# 4x4keyboard.net
KiCad netlist of a schematic drawn in EAGLE
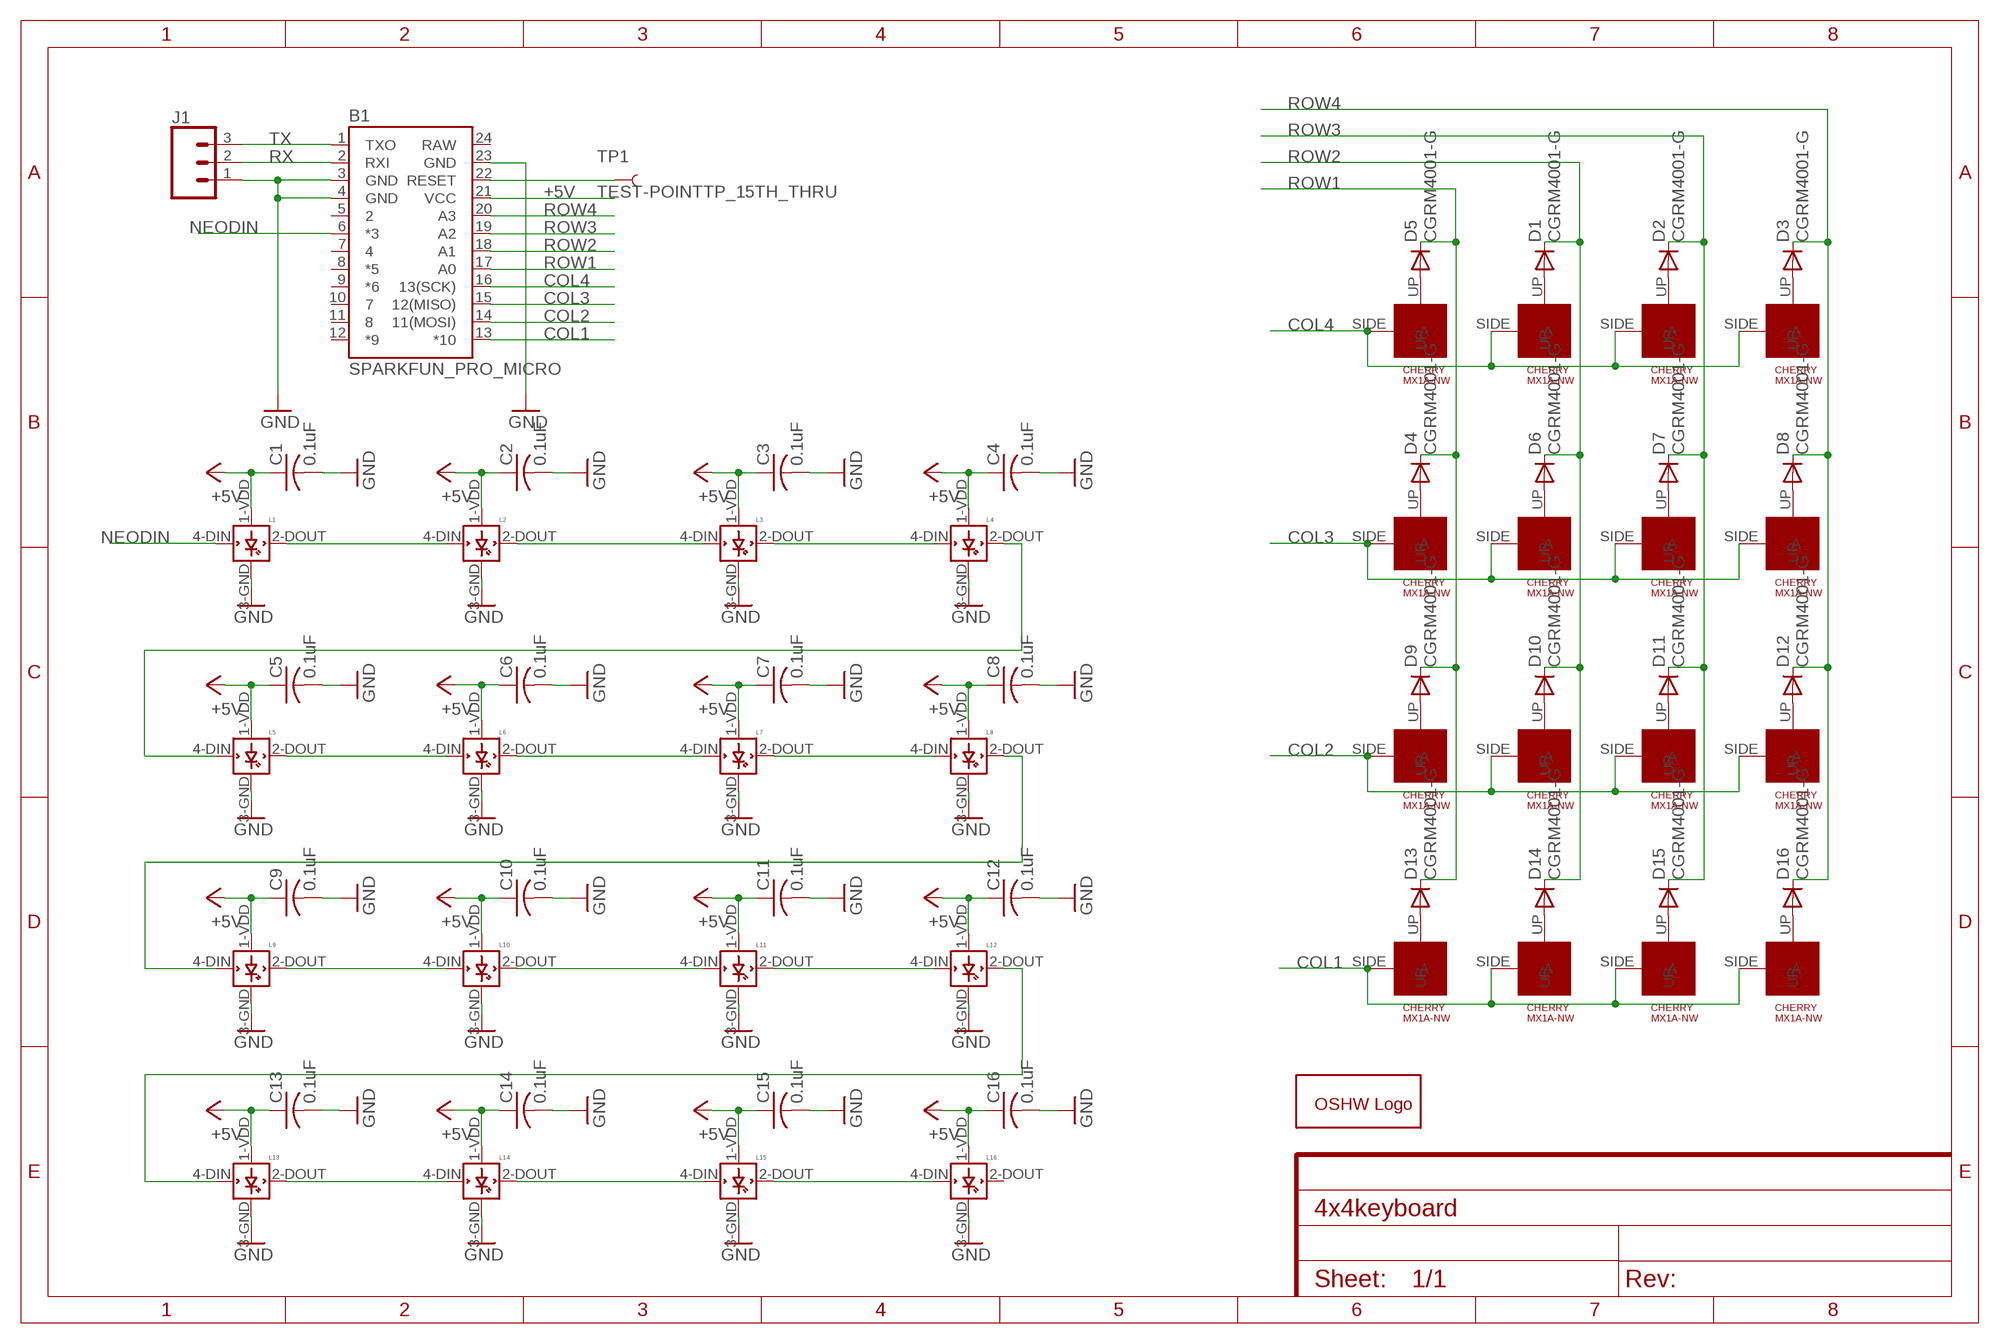
[diagram p0: schematic, sheet 1]

(export (version "E")
  (design (tool "Eeschema 10.0.6"))
  (components
    (comp (ref "B1")
      (value "SPARKFUN_PRO_MICRO")
      (footprint "eagle-import:SPARKFUN_PRO_MICRO")
      (libsource (lib "eagle-import") (part "SPARKFUN_PRO_MICRO"))
    )
    (comp (ref "C1")
      (value "0.1uF")
      (footprint "eagle-import:C0603")
      (libsource (lib "eagle-import") (part "C-USC0603"))
    )
    (comp (ref "C2")
      (value "0.1uF")
      (footprint "eagle-import:C0603")
      (libsource (lib "eagle-import") (part "C-USC0603"))
    )
    (comp (ref "C3")
      (value "0.1uF")
      (footprint "eagle-import:C0603")
      (libsource (lib "eagle-import") (part "C-USC0603"))
    )
    (comp (ref "C4")
      (value "0.1uF")
      (footprint "eagle-import:C0603")
      (libsource (lib "eagle-import") (part "C-USC0603"))
    )
    (comp (ref "C5")
      (value "0.1uF")
      (footprint "eagle-import:C0603")
      (libsource (lib "eagle-import") (part "C-USC0603"))
    )
    (comp (ref "C6")
      (value "0.1uF")
      (footprint "eagle-import:C0603")
      (libsource (lib "eagle-import") (part "C-USC0603"))
    )
    (comp (ref "C7")
      (value "0.1uF")
      (footprint "eagle-import:C0603")
      (libsource (lib "eagle-import") (part "C-USC0603"))
    )
    (comp (ref "C8")
      (value "0.1uF")
      (footprint "eagle-import:C0603")
      (libsource (lib "eagle-import") (part "C-USC0603"))
    )
    (comp (ref "C9")
      (value "0.1uF")
      (footprint "eagle-import:C0603")
      (libsource (lib "eagle-import") (part "C-USC0603"))
    )
    (comp (ref "C10")
      (value "0.1uF")
      (footprint "eagle-import:C0603")
      (libsource (lib "eagle-import") (part "C-USC0603"))
    )
    (comp (ref "C11")
      (value "0.1uF")
      (footprint "eagle-import:C0603")
      (libsource (lib "eagle-import") (part "C-USC0603"))
    )
    (comp (ref "C12")
      (value "0.1uF")
      (footprint "eagle-import:C0603")
      (libsource (lib "eagle-import") (part "C-USC0603"))
    )
    (comp (ref "C13")
      (value "0.1uF")
      (footprint "eagle-import:C0603")
      (libsource (lib "eagle-import") (part "C-USC0603"))
    )
    (comp (ref "C14")
      (value "0.1uF")
      (footprint "eagle-import:C0603")
      (libsource (lib "eagle-import") (part "C-USC0603"))
    )
    (comp (ref "C15")
      (value "0.1uF")
      (footprint "eagle-import:C0603")
      (libsource (lib "eagle-import") (part "C-USC0603"))
    )
    (comp (ref "C16")
      (value "0.1uF")
      (footprint "eagle-import:C0603")
      (libsource (lib "eagle-import") (part "C-USC0603"))
    )
    (comp (ref "D1")
      (value "CGRM4001-G")
      (footprint "eagle-import:SOD-123_MINI-SMA")
      (libsource (lib "eagle-import") (part "CGRM400-G1"))
    )
    (comp (ref "D2")
      (value "CGRM4001-G")
      (footprint "eagle-import:SOD-123_MINI-SMA")
      (libsource (lib "eagle-import") (part "CGRM400-G1"))
    )
    (comp (ref "D3")
      (value "CGRM4001-G")
      (footprint "eagle-import:SOD-123_MINI-SMA")
      (libsource (lib "eagle-import") (part "CGRM400-G1"))
    )
    (comp (ref "D4")
      (value "CGRM4001-G")
      (footprint "eagle-import:SOD-123_MINI-SMA")
      (libsource (lib "eagle-import") (part "CGRM400-G1"))
    )
    (comp (ref "D5")
      (value "CGRM4001-G")
      (footprint "eagle-import:SOD-123_MINI-SMA")
      (libsource (lib "eagle-import") (part "CGRM400-G1"))
    )
    (comp (ref "D6")
      (value "CGRM4001-G")
      (footprint "eagle-import:SOD-123_MINI-SMA")
      (libsource (lib "eagle-import") (part "CGRM400-G1"))
    )
    (comp (ref "D7")
      (value "CGRM4001-G")
      (footprint "eagle-import:SOD-123_MINI-SMA")
      (libsource (lib "eagle-import") (part "CGRM400-G1"))
    )
    (comp (ref "D8")
      (value "CGRM4001-G")
      (footprint "eagle-import:SOD-123_MINI-SMA")
      (libsource (lib "eagle-import") (part "CGRM400-G1"))
    )
    (comp (ref "D9")
      (value "CGRM4001-G")
      (footprint "eagle-import:SOD-123_MINI-SMA")
      (libsource (lib "eagle-import") (part "CGRM400-G1"))
    )
    (comp (ref "D10")
      (value "CGRM4001-G")
      (footprint "eagle-import:SOD-123_MINI-SMA")
      (libsource (lib "eagle-import") (part "CGRM400-G1"))
    )
    (comp (ref "D11")
      (value "CGRM4001-G")
      (footprint "eagle-import:SOD-123_MINI-SMA")
      (libsource (lib "eagle-import") (part "CGRM400-G1"))
    )
    (comp (ref "D12")
      (value "CGRM4001-G")
      (footprint "eagle-import:SOD-123_MINI-SMA")
      (libsource (lib "eagle-import") (part "CGRM400-G1"))
    )
    (comp (ref "D13")
      (value "CGRM4001-G")
      (footprint "eagle-import:SOD-123_MINI-SMA")
      (libsource (lib "eagle-import") (part "CGRM400-G1"))
    )
    (comp (ref "D14")
      (value "CGRM4001-G")
      (footprint "eagle-import:SOD-123_MINI-SMA")
      (libsource (lib "eagle-import") (part "CGRM400-G1"))
    )
    (comp (ref "D15")
      (value "CGRM4001-G")
      (footprint "eagle-import:SOD-123_MINI-SMA")
      (libsource (lib "eagle-import") (part "CGRM400-G1"))
    )
    (comp (ref "D16")
      (value "CGRM4001-G")
      (footprint "eagle-import:SOD-123_MINI-SMA")
      (libsource (lib "eagle-import") (part "CGRM400-G1"))
    )
    (comp (ref "GOLD_ORB_SM1")
      (value "OSHWLOGOLOGO5MM")
      (footprint "eagle-import:OSHW_5MM")
      (libsource (lib "eagle-import") (part "OSHWLOGOLOGO5MM"))
    )
    (comp (ref "J1")
      (value "CONN_03LOCK")
      (footprint "eagle-import:1X03_LOCK")
      (libsource (lib "eagle-import") (part "CONN_03LOCK"))
    )
    (comp (ref "L1")
      (value "WS2812B")
      (footprint "eagle-import:WS2812B")
      (libsource (lib "eagle-import") (part "WS2812B"))
    )
    (comp (ref "L2")
      (value "WS2812B")
      (footprint "eagle-import:WS2812B")
      (libsource (lib "eagle-import") (part "WS2812B"))
    )
    (comp (ref "L3")
      (value "WS2812B")
      (footprint "eagle-import:WS2812B")
      (libsource (lib "eagle-import") (part "WS2812B"))
    )
    (comp (ref "L4")
      (value "WS2812B")
      (footprint "eagle-import:WS2812B")
      (libsource (lib "eagle-import") (part "WS2812B"))
    )
    (comp (ref "L5")
      (value "WS2812B")
      (footprint "eagle-import:WS2812B")
      (libsource (lib "eagle-import") (part "WS2812B"))
    )
    (comp (ref "L6")
      (value "WS2812B")
      (footprint "eagle-import:WS2812B")
      (libsource (lib "eagle-import") (part "WS2812B"))
    )
    (comp (ref "L7")
      (value "WS2812B")
      (footprint "eagle-import:WS2812B")
      (libsource (lib "eagle-import") (part "WS2812B"))
    )
    (comp (ref "L8")
      (value "WS2812B")
      (footprint "eagle-import:WS2812B")
      (libsource (lib "eagle-import") (part "WS2812B"))
    )
    (comp (ref "L9")
      (value "WS2812B")
      (footprint "eagle-import:WS2812B")
      (libsource (lib "eagle-import") (part "WS2812B"))
    )
    (comp (ref "L10")
      (value "WS2812B")
      (footprint "eagle-import:WS2812B")
      (libsource (lib "eagle-import") (part "WS2812B"))
    )
    (comp (ref "L11")
      (value "WS2812B")
      (footprint "eagle-import:WS2812B")
      (libsource (lib "eagle-import") (part "WS2812B"))
    )
    (comp (ref "L12")
      (value "WS2812B")
      (footprint "eagle-import:WS2812B")
      (libsource (lib "eagle-import") (part "WS2812B"))
    )
    (comp (ref "L13")
      (value "WS2812B")
      (footprint "eagle-import:WS2812B")
      (libsource (lib "eagle-import") (part "WS2812B"))
    )
    (comp (ref "L14")
      (value "WS2812B")
      (footprint "eagle-import:WS2812B")
      (libsource (lib "eagle-import") (part "WS2812B"))
    )
    (comp (ref "L15")
      (value "WS2812B")
      (footprint "eagle-import:WS2812B")
      (libsource (lib "eagle-import") (part "WS2812B"))
    )
    (comp (ref "L16")
      (value "WS2812B")
      (footprint "eagle-import:WS2812B")
      (libsource (lib "eagle-import") (part "WS2812B"))
    )
    (comp (ref "TP1")
      (value "TEST-POINTTP_15TH_THRU")
      (footprint "eagle-import:TP_15TH")
      (libsource (lib "eagle-import") (part "TEST-POINTTP_15TH_THRU"))
    )
    (comp (ref "U$1")
      (value "CHERRY-MX1A-E1NW")
      (footprint "eagle-import:CHERRYMX-NN")
      (libsource (lib "eagle-import") (part "CHERRY-MX1A-E1NW"))
    )
    (comp (ref "U$2")
      (value "CHERRY-MX1A-E1NW")
      (footprint "eagle-import:CHERRYMX-NN")
      (libsource (lib "eagle-import") (part "CHERRY-MX1A-E1NW"))
    )
    (comp (ref "U$3")
      (value "CHERRY-MX1A-E1NW")
      (footprint "eagle-import:CHERRYMX-NN")
      (libsource (lib "eagle-import") (part "CHERRY-MX1A-E1NW"))
    )
    (comp (ref "U$4")
      (value "CHERRY-MX1A-E1NW")
      (footprint "eagle-import:CHERRYMX-NN")
      (libsource (lib "eagle-import") (part "CHERRY-MX1A-E1NW"))
    )
    (comp (ref "U$7")
      (value "CHERRY-MX1A-E1NW")
      (footprint "eagle-import:CHERRYMX-NN")
      (libsource (lib "eagle-import") (part "CHERRY-MX1A-E1NW"))
    )
    (comp (ref "U$8")
      (value "CHERRY-MX1A-E1NW")
      (footprint "eagle-import:CHERRYMX-NN")
      (libsource (lib "eagle-import") (part "CHERRY-MX1A-E1NW"))
    )
    (comp (ref "U$9")
      (value "CHERRY-MX1A-E1NW")
      (footprint "eagle-import:CHERRYMX-NN")
      (libsource (lib "eagle-import") (part "CHERRY-MX1A-E1NW"))
    )
    (comp (ref "U$10")
      (value "CHERRY-MX1A-E1NW")
      (footprint "eagle-import:CHERRYMX-NN")
      (libsource (lib "eagle-import") (part "CHERRY-MX1A-E1NW"))
    )
    (comp (ref "U$19")
      (value "CHERRY-MX1A-E1NW")
      (footprint "eagle-import:CHERRYMX-NN")
      (libsource (lib "eagle-import") (part "CHERRY-MX1A-E1NW"))
    )
    (comp (ref "U$20")
      (value "CHERRY-MX1A-E1NW")
      (footprint "eagle-import:CHERRYMX-NN")
      (libsource (lib "eagle-import") (part "CHERRY-MX1A-E1NW"))
    )
    (comp (ref "U$21")
      (value "CHERRY-MX1A-E1NW")
      (footprint "eagle-import:CHERRYMX-NN")
      (libsource (lib "eagle-import") (part "CHERRY-MX1A-E1NW"))
    )
    (comp (ref "U$22")
      (value "CHERRY-MX1A-E1NW")
      (footprint "eagle-import:CHERRYMX-NN")
      (libsource (lib "eagle-import") (part "CHERRY-MX1A-E1NW"))
    )
    (comp (ref "U$25")
      (value "CHERRY-MX1A-E1NW")
      (footprint "eagle-import:CHERRYMX-NN")
      (libsource (lib "eagle-import") (part "CHERRY-MX1A-E1NW"))
    )
    (comp (ref "U$26")
      (value "CHERRY-MX1A-E1NW")
      (footprint "eagle-import:CHERRYMX-NN")
      (libsource (lib "eagle-import") (part "CHERRY-MX1A-E1NW"))
    )
    (comp (ref "U$27")
      (value "CHERRY-MX1A-E1NW")
      (footprint "eagle-import:CHERRYMX-NN")
      (libsource (lib "eagle-import") (part "CHERRY-MX1A-E1NW"))
    )
    (comp (ref "U$28")
      (value "CHERRY-MX1A-E1NW")
      (footprint "eagle-import:CHERRYMX-NN")
      (libsource (lib "eagle-import") (part "CHERRY-MX1A-E1NW"))
    )
  )
  (nets
    (net (code "1") (name "+5V") (class "Default")
      (node (ref "B1") (pin "21") (pinfunction "VCC_21") (pintype "power_in"))
      (node (ref "C1") (pin "1") (pinfunction "1_1") (pintype "passive"))
      (node (ref "C10") (pin "1") (pinfunction "1_1") (pintype "passive"))
      (node (ref "C11") (pin "1") (pinfunction "1_1") (pintype "passive"))
      (node (ref "C12") (pin "1") (pinfunction "1_1") (pintype "passive"))
      (node (ref "C13") (pin "1") (pinfunction "1_1") (pintype "passive"))
      (node (ref "C14") (pin "1") (pinfunction "1_1") (pintype "passive"))
      (node (ref "C15") (pin "1") (pinfunction "1_1") (pintype "passive"))
      (node (ref "C16") (pin "1") (pinfunction "1_1") (pintype "passive"))
      (node (ref "C2") (pin "1") (pinfunction "1_1") (pintype "passive"))
      (node (ref "C3") (pin "1") (pinfunction "1_1") (pintype "passive"))
      (node (ref "C4") (pin "1") (pinfunction "1_1") (pintype "passive"))
      (node (ref "C5") (pin "1") (pinfunction "1_1") (pintype "passive"))
      (node (ref "C6") (pin "1") (pinfunction "1_1") (pintype "passive"))
      (node (ref "C7") (pin "1") (pinfunction "1_1") (pintype "passive"))
      (node (ref "C8") (pin "1") (pinfunction "1_1") (pintype "passive"))
      (node (ref "C9") (pin "1") (pinfunction "1_1") (pintype "passive"))
      (node (ref "L1") (pin "1-VDD") (pinfunction "VDD_1-VDD") (pintype "bidirectional"))
      (node (ref "L10") (pin "1-VDD") (pinfunction "VDD_1-VDD") (pintype "bidirectional"))
      (node (ref "L11") (pin "1-VDD") (pinfunction "VDD_1-VDD") (pintype "bidirectional"))
      (node (ref "L12") (pin "1-VDD") (pinfunction "VDD_1-VDD") (pintype "bidirectional"))
      (node (ref "L13") (pin "1-VDD") (pinfunction "VDD_1-VDD") (pintype "bidirectional"))
      (node (ref "L14") (pin "1-VDD") (pinfunction "VDD_1-VDD") (pintype "bidirectional"))
      (node (ref "L15") (pin "1-VDD") (pinfunction "VDD_1-VDD") (pintype "bidirectional"))
      (node (ref "L16") (pin "1-VDD") (pinfunction "VDD_1-VDD") (pintype "bidirectional"))
      (node (ref "L2") (pin "1-VDD") (pinfunction "VDD_1-VDD") (pintype "bidirectional"))
      (node (ref "L3") (pin "1-VDD") (pinfunction "VDD_1-VDD") (pintype "bidirectional"))
      (node (ref "L4") (pin "1-VDD") (pinfunction "VDD_1-VDD") (pintype "bidirectional"))
      (node (ref "L5") (pin "1-VDD") (pinfunction "VDD_1-VDD") (pintype "bidirectional"))
      (node (ref "L6") (pin "1-VDD") (pinfunction "VDD_1-VDD") (pintype "bidirectional"))
      (node (ref "L7") (pin "1-VDD") (pinfunction "VDD_1-VDD") (pintype "bidirectional"))
      (node (ref "L8") (pin "1-VDD") (pinfunction "VDD_1-VDD") (pintype "bidirectional"))
      (node (ref "L9") (pin "1-VDD") (pinfunction "VDD_1-VDD") (pintype "bidirectional"))
    )
    (net (code "2") (name "/COL1") (class "Default")
      (node (ref "B1") (pin "13") (pinfunction "*10_13") (pintype "bidirectional"))
      (node (ref "U$25") (pin "SIDE") (pinfunction "A_SIDE") (pintype "bidirectional"))
      (node (ref "U$26") (pin "SIDE") (pinfunction "A_SIDE") (pintype "bidirectional"))
      (node (ref "U$27") (pin "SIDE") (pinfunction "A_SIDE") (pintype "bidirectional"))
      (node (ref "U$28") (pin "SIDE") (pinfunction "A_SIDE") (pintype "bidirectional"))
    )
    (net (code "3") (name "/COL2") (class "Default")
      (node (ref "B1") (pin "14") (pinfunction "11(MOSI)_14") (pintype "bidirectional"))
      (node (ref "U$10") (pin "SIDE") (pinfunction "A_SIDE") (pintype "bidirectional"))
      (node (ref "U$7") (pin "SIDE") (pinfunction "A_SIDE") (pintype "bidirectional"))
      (node (ref "U$8") (pin "SIDE") (pinfunction "A_SIDE") (pintype "bidirectional"))
      (node (ref "U$9") (pin "SIDE") (pinfunction "A_SIDE") (pintype "bidirectional"))
    )
    (net (code "4") (name "/COL3") (class "Default")
      (node (ref "B1") (pin "15") (pinfunction "12(MISO)_15") (pintype "bidirectional"))
      (node (ref "U$1") (pin "SIDE") (pinfunction "A_SIDE") (pintype "bidirectional"))
      (node (ref "U$2") (pin "SIDE") (pinfunction "A_SIDE") (pintype "bidirectional"))
      (node (ref "U$3") (pin "SIDE") (pinfunction "A_SIDE") (pintype "bidirectional"))
      (node (ref "U$4") (pin "SIDE") (pinfunction "A_SIDE") (pintype "bidirectional"))
    )
    (net (code "5") (name "/COL4") (class "Default")
      (node (ref "B1") (pin "16") (pinfunction "13(SCK)_16") (pintype "bidirectional"))
      (node (ref "U$19") (pin "SIDE") (pinfunction "A_SIDE") (pintype "bidirectional"))
      (node (ref "U$20") (pin "SIDE") (pinfunction "A_SIDE") (pintype "bidirectional"))
      (node (ref "U$21") (pin "SIDE") (pinfunction "A_SIDE") (pintype "bidirectional"))
      (node (ref "U$22") (pin "SIDE") (pinfunction "A_SIDE") (pintype "bidirectional"))
    )
    (net (code "6") (name "/NEODIN") (class "Default")
      (node (ref "B1") (pin "6") (pinfunction "*3_6") (pintype "bidirectional"))
      (node (ref "L1") (pin "4-DIN") (pinfunction "DIN_4-DIN") (pintype "input"))
    )
    (net (code "7") (name "/RAW") (class "Default")
      (node (ref "B1") (pin "24") (pinfunction "RAW_24") (pintype "power_in"))
    )
    (net (code "8") (name "/ROW1") (class "Default")
      (node (ref "B1") (pin "17") (pinfunction "A0_17") (pintype "bidirectional"))
      (node (ref "D13") (pin "C") (pinfunction "C_C") (pintype "passive"))
      (node (ref "D4") (pin "C") (pinfunction "C_C") (pintype "passive"))
      (node (ref "D5") (pin "C") (pinfunction "C_C") (pintype "passive"))
      (node (ref "D9") (pin "C") (pinfunction "C_C") (pintype "passive"))
    )
    (net (code "9") (name "/ROW2") (class "Default")
      (node (ref "B1") (pin "18") (pinfunction "A1_18") (pintype "bidirectional"))
      (node (ref "D1") (pin "C") (pinfunction "C_C") (pintype "passive"))
      (node (ref "D10") (pin "C") (pinfunction "C_C") (pintype "passive"))
      (node (ref "D14") (pin "C") (pinfunction "C_C") (pintype "passive"))
      (node (ref "D6") (pin "C") (pinfunction "C_C") (pintype "passive"))
    )
    (net (code "10") (name "/ROW3") (class "Default")
      (node (ref "B1") (pin "19") (pinfunction "A2_19") (pintype "bidirectional"))
      (node (ref "D11") (pin "C") (pinfunction "C_C") (pintype "passive"))
      (node (ref "D15") (pin "C") (pinfunction "C_C") (pintype "passive"))
      (node (ref "D2") (pin "C") (pinfunction "C_C") (pintype "passive"))
      (node (ref "D7") (pin "C") (pinfunction "C_C") (pintype "passive"))
    )
    (net (code "11") (name "/ROW4") (class "Default")
      (node (ref "B1") (pin "20") (pinfunction "A3_20") (pintype "bidirectional"))
      (node (ref "D12") (pin "C") (pinfunction "C_C") (pintype "passive"))
      (node (ref "D16") (pin "C") (pinfunction "C_C") (pintype "passive"))
      (node (ref "D3") (pin "C") (pinfunction "C_C") (pintype "passive"))
      (node (ref "D8") (pin "C") (pinfunction "C_C") (pintype "passive"))
    )
    (net (code "12") (name "/RX") (class "Default")
      (node (ref "B1") (pin "2") (pinfunction "RXI_2") (pintype "bidirectional"))
      (node (ref "J1") (pin "2") (pinfunction "2_2") (pintype "passive"))
    )
    (net (code "13") (name "/TX") (class "Default")
      (node (ref "B1") (pin "1") (pinfunction "TXO_1") (pintype "bidirectional"))
      (node (ref "J1") (pin "3") (pinfunction "3_3") (pintype "passive"))
    )
    (net (code "14") (name "GND") (class "Default")
      (node (ref "B1") (pin "23") (pinfunction "GND_23") (pintype "power_in"))
      (node (ref "B1") (pin "3") (pinfunction "GND_3") (pintype "power_in"))
      (node (ref "B1") (pin "4") (pinfunction "GND_4") (pintype "power_in"))
      (node (ref "C1") (pin "2") (pinfunction "2_2") (pintype "passive"))
      (node (ref "C10") (pin "2") (pinfunction "2_2") (pintype "passive"))
      (node (ref "C11") (pin "2") (pinfunction "2_2") (pintype "passive"))
      (node (ref "C12") (pin "2") (pinfunction "2_2") (pintype "passive"))
      (node (ref "C13") (pin "2") (pinfunction "2_2") (pintype "passive"))
      (node (ref "C14") (pin "2") (pinfunction "2_2") (pintype "passive"))
      (node (ref "C15") (pin "2") (pinfunction "2_2") (pintype "passive"))
      (node (ref "C16") (pin "2") (pinfunction "2_2") (pintype "passive"))
      (node (ref "C2") (pin "2") (pinfunction "2_2") (pintype "passive"))
      (node (ref "C3") (pin "2") (pinfunction "2_2") (pintype "passive"))
      (node (ref "C4") (pin "2") (pinfunction "2_2") (pintype "passive"))
      (node (ref "C5") (pin "2") (pinfunction "2_2") (pintype "passive"))
      (node (ref "C6") (pin "2") (pinfunction "2_2") (pintype "passive"))
      (node (ref "C7") (pin "2") (pinfunction "2_2") (pintype "passive"))
      (node (ref "C8") (pin "2") (pinfunction "2_2") (pintype "passive"))
      (node (ref "C9") (pin "2") (pinfunction "2_2") (pintype "passive"))
      (node (ref "J1") (pin "1") (pinfunction "1_1") (pintype "passive"))
      (node (ref "L1") (pin "3-GND") (pinfunction "GND_3-GND") (pintype "bidirectional"))
      (node (ref "L10") (pin "3-GND") (pinfunction "GND_3-GND") (pintype "bidirectional"))
      (node (ref "L11") (pin "3-GND") (pinfunction "GND_3-GND") (pintype "bidirectional"))
      (node (ref "L12") (pin "3-GND") (pinfunction "GND_3-GND") (pintype "bidirectional"))
      (node (ref "L13") (pin "3-GND") (pinfunction "GND_3-GND") (pintype "bidirectional"))
      (node (ref "L14") (pin "3-GND") (pinfunction "GND_3-GND") (pintype "bidirectional"))
      (node (ref "L15") (pin "3-GND") (pinfunction "GND_3-GND") (pintype "bidirectional"))
      (node (ref "L16") (pin "3-GND") (pinfunction "GND_3-GND") (pintype "bidirectional"))
      (node (ref "L2") (pin "3-GND") (pinfunction "GND_3-GND") (pintype "bidirectional"))
      (node (ref "L3") (pin "3-GND") (pinfunction "GND_3-GND") (pintype "bidirectional"))
      (node (ref "L4") (pin "3-GND") (pinfunction "GND_3-GND") (pintype "bidirectional"))
      (node (ref "L5") (pin "3-GND") (pinfunction "GND_3-GND") (pintype "bidirectional"))
      (node (ref "L6") (pin "3-GND") (pinfunction "GND_3-GND") (pintype "bidirectional"))
      (node (ref "L7") (pin "3-GND") (pinfunction "GND_3-GND") (pintype "bidirectional"))
      (node (ref "L8") (pin "3-GND") (pinfunction "GND_3-GND") (pintype "bidirectional"))
      (node (ref "L9") (pin "3-GND") (pinfunction "GND_3-GND") (pintype "bidirectional"))
    )
    (net (code "15") (name "Net-(B1-RESET)") (class "Default")
      (node (ref "B1") (pin "22") (pinfunction "RESET_22") (pintype "bidirectional"))
      (node (ref "TP1") (pin "P$1") (pinfunction "1_P$1") (pintype "bidirectional"))
    )
    (net (code "16") (name "Net-(D1-PadA)") (class "Default")
      (node (ref "D1") (pin "A") (pinfunction "A_A") (pintype "passive"))
      (node (ref "U$20") (pin "UP") (pinfunction "UP_UP") (pintype "bidirectional"))
    )
    (net (code "17") (name "Net-(D2-PadA)") (class "Default")
      (node (ref "D2") (pin "A") (pinfunction "A_A") (pintype "passive"))
      (node (ref "U$21") (pin "UP") (pinfunction "UP_UP") (pintype "bidirectional"))
    )
    (net (code "18") (name "Net-(D3-PadA)") (class "Default")
      (node (ref "D3") (pin "A") (pinfunction "A_A") (pintype "passive"))
      (node (ref "U$22") (pin "UP") (pinfunction "UP_UP") (pintype "bidirectional"))
    )
    (net (code "19") (name "Net-(D4-PadA)") (class "Default")
      (node (ref "D4") (pin "A") (pinfunction "A_A") (pintype "passive"))
      (node (ref "U$2") (pin "UP") (pinfunction "UP_UP") (pintype "bidirectional"))
    )
    (net (code "20") (name "Net-(D5-PadA)") (class "Default")
      (node (ref "D5") (pin "A") (pinfunction "A_A") (pintype "passive"))
      (node (ref "U$19") (pin "UP") (pinfunction "UP_UP") (pintype "bidirectional"))
    )
    (net (code "21") (name "Net-(D6-PadA)") (class "Default")
      (node (ref "D6") (pin "A") (pinfunction "A_A") (pintype "passive"))
      (node (ref "U$1") (pin "UP") (pinfunction "UP_UP") (pintype "bidirectional"))
    )
    (net (code "22") (name "Net-(D7-PadA)") (class "Default")
      (node (ref "D7") (pin "A") (pinfunction "A_A") (pintype "passive"))
      (node (ref "U$3") (pin "UP") (pinfunction "UP_UP") (pintype "bidirectional"))
    )
    (net (code "23") (name "Net-(D8-PadA)") (class "Default")
      (node (ref "D8") (pin "A") (pinfunction "A_A") (pintype "passive"))
      (node (ref "U$4") (pin "UP") (pinfunction "UP_UP") (pintype "bidirectional"))
    )
    (net (code "24") (name "Net-(D9-PadA)") (class "Default")
      (node (ref "D9") (pin "A") (pinfunction "A_A") (pintype "passive"))
      (node (ref "U$7") (pin "UP") (pinfunction "UP_UP") (pintype "bidirectional"))
    )
    (net (code "25") (name "Net-(D10-PadA)") (class "Default")
      (node (ref "D10") (pin "A") (pinfunction "A_A") (pintype "passive"))
      (node (ref "U$8") (pin "UP") (pinfunction "UP_UP") (pintype "bidirectional"))
    )
    (net (code "26") (name "Net-(D11-PadA)") (class "Default")
      (node (ref "D11") (pin "A") (pinfunction "A_A") (pintype "passive"))
      (node (ref "U$9") (pin "UP") (pinfunction "UP_UP") (pintype "bidirectional"))
    )
    (net (code "27") (name "Net-(D12-PadA)") (class "Default")
      (node (ref "D12") (pin "A") (pinfunction "A_A") (pintype "passive"))
      (node (ref "U$10") (pin "UP") (pinfunction "UP_UP") (pintype "bidirectional"))
    )
    (net (code "28") (name "Net-(D13-PadA)") (class "Default")
      (node (ref "D13") (pin "A") (pinfunction "A_A") (pintype "passive"))
      (node (ref "U$25") (pin "UP") (pinfunction "UP_UP") (pintype "bidirectional"))
    )
    (net (code "29") (name "Net-(D14-PadA)") (class "Default")
      (node (ref "D14") (pin "A") (pinfunction "A_A") (pintype "passive"))
      (node (ref "U$26") (pin "UP") (pinfunction "UP_UP") (pintype "bidirectional"))
    )
    (net (code "30") (name "Net-(D15-PadA)") (class "Default")
      (node (ref "D15") (pin "A") (pinfunction "A_A") (pintype "passive"))
      (node (ref "U$27") (pin "UP") (pinfunction "UP_UP") (pintype "bidirectional"))
    )
    (net (code "31") (name "Net-(D16-PadA)") (class "Default")
      (node (ref "D16") (pin "A") (pinfunction "A_A") (pintype "passive"))
      (node (ref "U$28") (pin "UP") (pinfunction "UP_UP") (pintype "bidirectional"))
    )
    (net (code "32") (name "Net-(L1-DOUT)") (class "Default")
      (node (ref "L1") (pin "2-DOUT") (pinfunction "DOUT_2-DOUT") (pintype "output"))
      (node (ref "L2") (pin "4-DIN") (pinfunction "DIN_4-DIN") (pintype "input"))
    )
    (net (code "33") (name "Net-(L2-DOUT)") (class "Default")
      (node (ref "L2") (pin "2-DOUT") (pinfunction "DOUT_2-DOUT") (pintype "output"))
      (node (ref "L3") (pin "4-DIN") (pinfunction "DIN_4-DIN") (pintype "input"))
    )
    (net (code "34") (name "Net-(L3-DOUT)") (class "Default")
      (node (ref "L3") (pin "2-DOUT") (pinfunction "DOUT_2-DOUT") (pintype "output"))
      (node (ref "L4") (pin "4-DIN") (pinfunction "DIN_4-DIN") (pintype "input"))
    )
    (net (code "35") (name "Net-(L4-DOUT)") (class "Default")
      (node (ref "L4") (pin "2-DOUT") (pinfunction "DOUT_2-DOUT") (pintype "output"))
      (node (ref "L5") (pin "4-DIN") (pinfunction "DIN_4-DIN") (pintype "input"))
    )
    (net (code "36") (name "Net-(L5-DOUT)") (class "Default")
      (node (ref "L5") (pin "2-DOUT") (pinfunction "DOUT_2-DOUT") (pintype "output"))
      (node (ref "L6") (pin "4-DIN") (pinfunction "DIN_4-DIN") (pintype "input"))
    )
    (net (code "37") (name "Net-(L6-DOUT)") (class "Default")
      (node (ref "L6") (pin "2-DOUT") (pinfunction "DOUT_2-DOUT") (pintype "output"))
      (node (ref "L7") (pin "4-DIN") (pinfunction "DIN_4-DIN") (pintype "input"))
    )
    (net (code "38") (name "Net-(L7-DOUT)") (class "Default")
      (node (ref "L7") (pin "2-DOUT") (pinfunction "DOUT_2-DOUT") (pintype "output"))
      (node (ref "L8") (pin "4-DIN") (pinfunction "DIN_4-DIN") (pintype "input"))
    )
    (net (code "39") (name "Net-(L8-DOUT)") (class "Default")
      (node (ref "L8") (pin "2-DOUT") (pinfunction "DOUT_2-DOUT") (pintype "output"))
      (node (ref "L9") (pin "4-DIN") (pinfunction "DIN_4-DIN") (pintype "input"))
    )
    (net (code "40") (name "Net-(L10-DIN)") (class "Default")
      (node (ref "L10") (pin "4-DIN") (pinfunction "DIN_4-DIN") (pintype "input"))
      (node (ref "L9") (pin "2-DOUT") (pinfunction "DOUT_2-DOUT") (pintype "output"))
    )
    (net (code "41") (name "Net-(L10-DOUT)") (class "Default")
      (node (ref "L10") (pin "2-DOUT") (pinfunction "DOUT_2-DOUT") (pintype "output"))
      (node (ref "L11") (pin "4-DIN") (pinfunction "DIN_4-DIN") (pintype "input"))
    )
    (net (code "42") (name "Net-(L11-DOUT)") (class "Default")
      (node (ref "L11") (pin "2-DOUT") (pinfunction "DOUT_2-DOUT") (pintype "output"))
      (node (ref "L12") (pin "4-DIN") (pinfunction "DIN_4-DIN") (pintype "input"))
    )
    (net (code "43") (name "Net-(L12-DOUT)") (class "Default")
      (node (ref "L12") (pin "2-DOUT") (pinfunction "DOUT_2-DOUT") (pintype "output"))
      (node (ref "L13") (pin "4-DIN") (pinfunction "DIN_4-DIN") (pintype "input"))
    )
    (net (code "44") (name "Net-(L13-DOUT)") (class "Default")
      (node (ref "L13") (pin "2-DOUT") (pinfunction "DOUT_2-DOUT") (pintype "output"))
      (node (ref "L14") (pin "4-DIN") (pinfunction "DIN_4-DIN") (pintype "input"))
    )
    (net (code "45") (name "Net-(L14-DOUT)") (class "Default")
      (node (ref "L14") (pin "2-DOUT") (pinfunction "DOUT_2-DOUT") (pintype "output"))
      (node (ref "L15") (pin "4-DIN") (pinfunction "DIN_4-DIN") (pintype "input"))
    )
    (net (code "46") (name "Net-(L15-DOUT)") (class "Default")
      (node (ref "L15") (pin "2-DOUT") (pinfunction "DOUT_2-DOUT") (pintype "output"))
      (node (ref "L16") (pin "4-DIN") (pinfunction "DIN_4-DIN") (pintype "input"))
    )
    (net (code "47") (name "unconnected-(B1-*5-Pad8)") (class "Default")
      (node (ref "B1") (pin "8") (pinfunction "*5_8") (pintype "bidirectional"))
    )
    (net (code "48") (name "unconnected-(B1-*6-Pad9)") (class "Default")
      (node (ref "B1") (pin "9") (pinfunction "*6_9") (pintype "bidirectional"))
    )
    (net (code "49") (name "unconnected-(B1-*9-Pad12)") (class "Default")
      (node (ref "B1") (pin "12") (pinfunction "*9_12") (pintype "bidirectional"))
    )
    (net (code "50") (name "unconnected-(B1-2-Pad5)") (class "Default")
      (node (ref "B1") (pin "5") (pinfunction "2_5") (pintype "bidirectional"))
    )
    (net (code "51") (name "unconnected-(B1-4-Pad7)") (class "Default")
      (node (ref "B1") (pin "7") (pinfunction "4_7") (pintype "bidirectional"))
    )
    (net (code "52") (name "unconnected-(B1-7-Pad10)") (class "Default")
      (node (ref "B1") (pin "10") (pinfunction "7_10") (pintype "bidirectional"))
    )
    (net (code "53") (name "unconnected-(B1-8-Pad11)") (class "Default")
      (node (ref "B1") (pin "11") (pinfunction "8_11") (pintype "bidirectional"))
    )
    (net (code "54") (name "unconnected-(L16-DOUT-Pad2-DOUT)") (class "Default")
      (node (ref "L16") (pin "2-DOUT") (pinfunction "DOUT_2-DOUT") (pintype "output"))
    )
  )
)
